# converter.net
KiCad netlist of a schematic drawn in Altium Designer
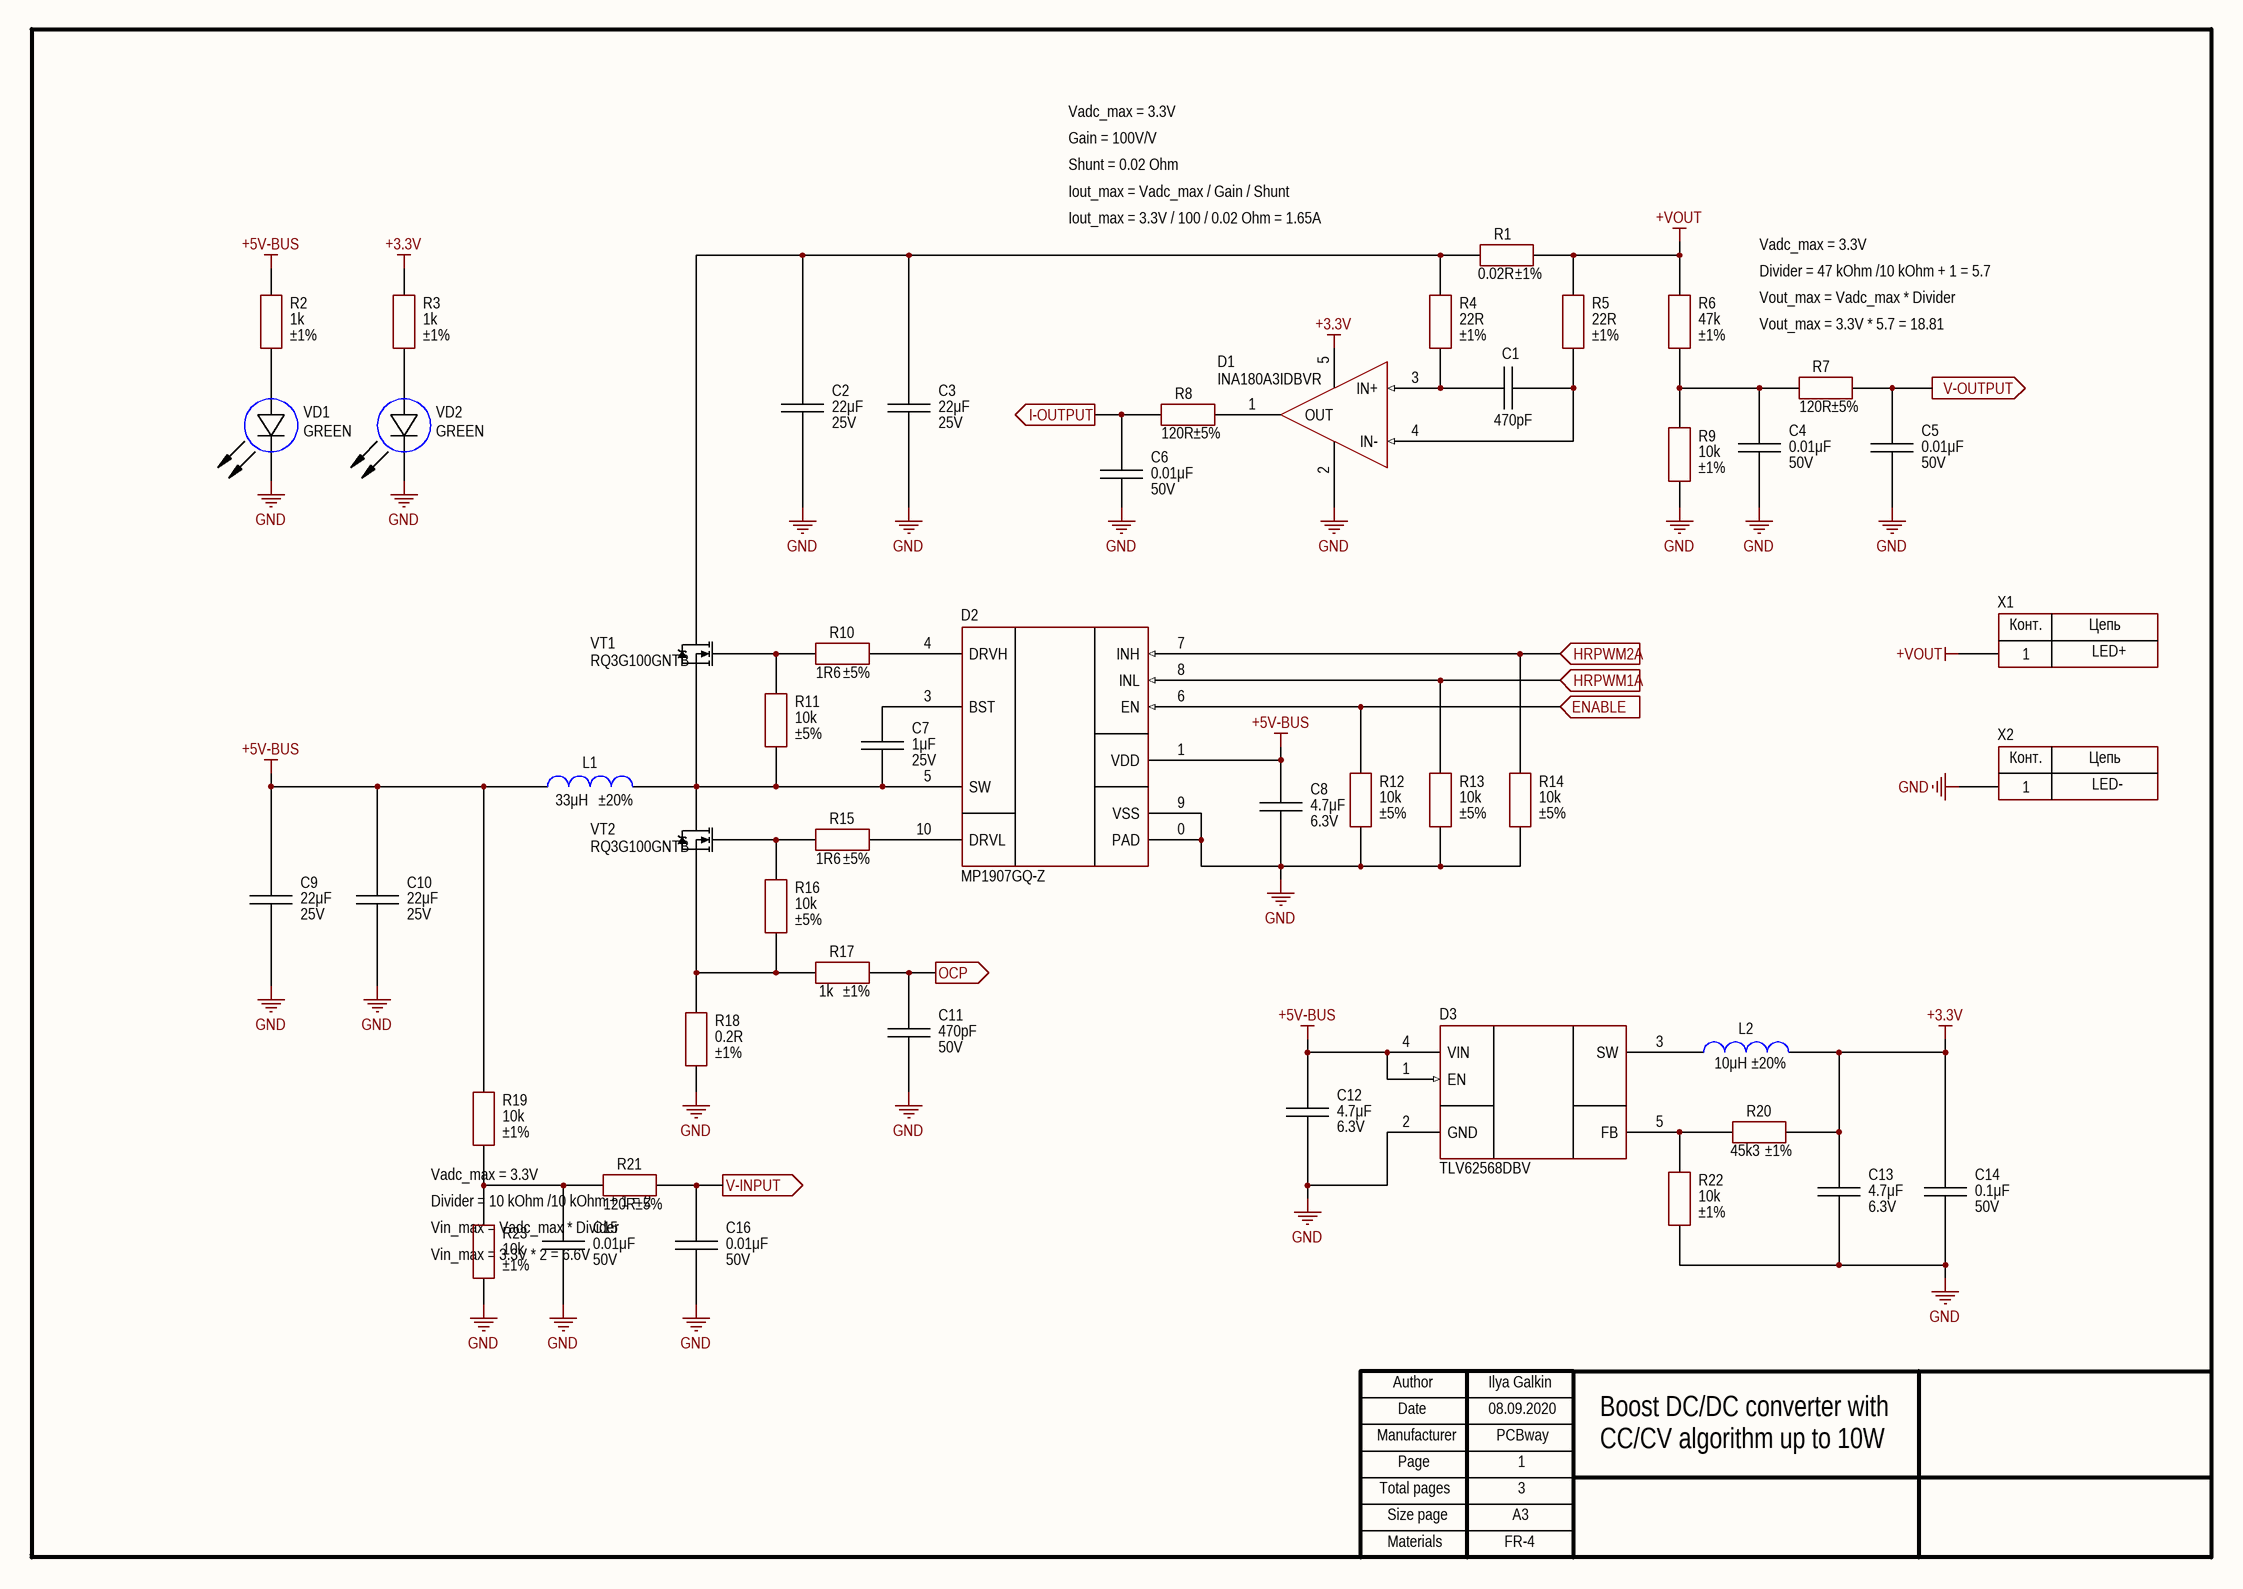
[diagram p0: converter.SchDoc]

(export (version "E")
  (design (tool "Eeschema 10.0.6"))
  (components
    (comp (ref "C1")
      (value "470pF")
      (footprint "CAP: 0603")
      (fields
        (field (name "MANUFACTURER") "Yageo")
        (field (name "PARTNUMBER") "CL10C471JB8NNNC")
        (field (name "VALUEMANUFACTURERPARTNUMBER") "Ceramic capacitor, 470pF, NPO, ±5%, 50V, 0603, -55...+125°C")
      )
      (libsource (lib "Capacitor") (part "Ceramic_0603"))
    )
    (comp (ref "C2")
      (value "22μF")
      (footprint "CAP: 1210")
      (fields
        (field (name "MANUFACTURER") "Samsung")
        (field (name "PARTNUMBER") "CL32B226KAJNNNE")
        (field (name "VALUEMANUFACTURERPARTNUMBER") "Ceramic capacitor, 22μF, X7R, ±10%, 25V, 1210, -55...+125°C")
        (field (name "VOLTAGE") "25V")
      )
      (libsource (lib "capacitor") (part "Ceramic_1210"))
    )
    (comp (ref "C3")
      (value "22μF")
      (footprint "CAP: 1210")
      (fields
        (field (name "MANUFACTURER") "Samsung")
        (field (name "PARTNUMBER") "CL32B226KAJNNNE")
        (field (name "VALUEMANUFACTURERPARTNUMBER") "Ceramic capacitor, 22μF, X7R, ±10%, 25V, 1210, -55...+125°C")
        (field (name "VOLTAGE") "25V")
      )
      (libsource (lib "capacitor") (part "Ceramic_1210"))
    )
    (comp (ref "C4")
      (value "0.01μF")
      (footprint "CAP: 0603")
      (fields
        (field (name "MANUFACTURER") "Samsung")
        (field (name "PARTNUMBER") "CL10B103KB8NNNC")
        (field (name "VALUEMANUFACTURERPARTNUMBER") "Ceramic capacitor, 0.01μF, X7R, ±10%, 50V, 0603, -55...+125°C")
        (field (name "VOLTAGE") "50V")
      )
      (libsource (lib "capacitor") (part "Ceramic_0603"))
    )
    (comp (ref "C5")
      (value "0.01μF")
      (footprint "CAP: 0603")
      (fields
        (field (name "MANUFACTURER") "Samsung")
        (field (name "PARTNUMBER") "CL10B103KB8NNNC")
        (field (name "VALUEMANUFACTURERPARTNUMBER") "Ceramic capacitor, 0.01μF, X7R, ±10%, 50V, 0603, -55...+125°C")
        (field (name "VOLTAGE") "50V")
      )
      (libsource (lib "capacitor") (part "Ceramic_0603"))
    )
    (comp (ref "C6")
      (value "0.01μF")
      (footprint "CAP: 0603")
      (fields
        (field (name "MANUFACTURER") "Samsung")
        (field (name "PARTNUMBER") "CL10B103KB8NNNC")
        (field (name "VALUEMANUFACTURERPARTNUMBER") "Ceramic capacitor, 0.01μF, X7R, ±10%, 50V, 0603, -55...+125°C")
        (field (name "VOLTAGE") "50V")
      )
      (libsource (lib "capacitor") (part "Ceramic_0603"))
    )
    (comp (ref "C7")
      (value "1μF")
      (footprint "CAP: 0603")
      (fields
        (field (name "MANUFACTURER") "Samsung")
        (field (name "PARTNUMBER") "CL10B105KA8NNNC")
        (field (name "VALUEMANUFACTURERPARTNUMBER") "Ceramic capacitor, 1μF, X7R, ±10%, 25V, 0603, -55...+125°C")
        (field (name "VOLTAGE") "25V")
      )
      (libsource (lib "capacitor") (part "Ceramic_0603"))
    )
    (comp (ref "C8")
      (value "4.7μF")
      (footprint "CAP: 0603")
      (fields
        (field (name "MANUFACTURER") "Samsung")
        (field (name "PARTNUMBER") "CL10B475KQ8NQNC")
        (field (name "VALUEMANUFACTURERPARTNUMBER") "Ceramic capacitor, 4.7μF, X7R, ±10%, 6.3V, 0603, -55...+125°C")
        (field (name "VOLTAGE") "6.3V")
      )
      (libsource (lib "capacitor") (part "Ceramic_0603"))
    )
    (comp (ref "C9")
      (value "22μF")
      (footprint "CAP: 1210")
      (fields
        (field (name "MANUFACTURER") "Samsung")
        (field (name "PARTNUMBER") "CL32B226KAJNNNE")
        (field (name "VALUEMANUFACTURERPARTNUMBER") "Ceramic capacitor, 22μF, X7R, ±10%, 25V, 1210, -55...+125°C")
        (field (name "VOLTAGE") "25V")
      )
      (libsource (lib "capacitor") (part "Ceramic_1210"))
    )
    (comp (ref "C10")
      (value "22μF")
      (footprint "CAP: 1210")
      (fields
        (field (name "MANUFACTURER") "Samsung")
        (field (name "PARTNUMBER") "CL32B226KAJNNNE")
        (field (name "VALUEMANUFACTURERPARTNUMBER") "Ceramic capacitor, 22μF, X7R, ±10%, 25V, 1210, -55...+125°C")
        (field (name "VOLTAGE") "25V")
      )
      (libsource (lib "capacitor") (part "Ceramic_1210"))
    )
    (comp (ref "C11")
      (value "470pF")
      (footprint "CAP: 0603")
      (fields
        (field (name "MANUFACTURER") "Yageo")
        (field (name "PARTNUMBER") "CL10C471JB8NNNC")
        (field (name "VALUEMANUFACTURERPARTNUMBER") "Ceramic capacitor, 470pF, NPO, ±5%, 50V, 0603, -55...+125°C")
        (field (name "VOLTAGE") "50V")
      )
      (libsource (lib "Capacitor") (part "Ceramic_0603"))
    )
    (comp (ref "C12")
      (value "4.7μF")
      (footprint "CAP: 0603")
      (fields
        (field (name "MANUFACTURER") "Samsung")
        (field (name "PARTNUMBER") "CL10B475KQ8NQNC")
        (field (name "VALUEMANUFACTURERPARTNUMBER") "Ceramic capacitor, 4.7μF, X7R, ±10%, 6.3V, 0603, -55...+125°C")
        (field (name "VOLTAGE") "6.3V")
      )
      (libsource (lib "capacitor") (part "Ceramic_0603"))
    )
    (comp (ref "C13")
      (value "4.7μF")
      (footprint "CAP: 0603")
      (fields
        (field (name "MANUFACTURER") "Samsung")
        (field (name "PARTNUMBER") "CL10B475KQ8NQNC")
        (field (name "VALUEMANUFACTURERPARTNUMBER") "Ceramic capacitor, 4.7μF, X7R, ±10%, 6.3V, 0603, -55...+125°C")
        (field (name "VOLTAGE") "6.3V")
      )
      (libsource (lib "capacitor") (part "Ceramic_0603"))
    )
    (comp (ref "C14")
      (value "0.1μF")
      (footprint "CAP: 0603")
      (fields
        (field (name "MANUFACTURER") "Samsung")
        (field (name "PARTNUMBER") "CL10B104KB8NNNL")
        (field (name "VALUEMANUFACTURERPARTNUMBER") "Ceramic capacitor, 0.1μF, X7R, ±10%, 50V, 0603, -55...+125°C")
        (field (name "VOLTAGE") "50V")
      )
      (libsource (lib "capacitor") (part "Ceramic_0603"))
    )
    (comp (ref "C15")
      (value "0.01μF")
      (footprint "CAP: 0603")
      (fields
        (field (name "MANUFACTURER") "Samsung")
        (field (name "PARTNUMBER") "CL10B103KB8NNNC")
        (field (name "VALUEMANUFACTURERPARTNUMBER") "Ceramic capacitor, 0.01μF, X7R, ±10%, 50V, 0603, -55...+125°C")
        (field (name "VOLTAGE") "50V")
      )
      (libsource (lib "capacitor") (part "Ceramic_0603"))
    )
    (comp (ref "C16")
      (value "0.01μF")
      (footprint "CAP: 0603")
      (fields
        (field (name "MANUFACTURER") "Samsung")
        (field (name "PARTNUMBER") "CL10B103KB8NNNC")
        (field (name "VALUEMANUFACTURERPARTNUMBER") "Ceramic capacitor, 0.01μF, X7R, ±10%, 50V, 0603, -55...+125°C")
        (field (name "VOLTAGE") "50V")
      )
      (libsource (lib "capacitor") (part "Ceramic_0603"))
    )
    (comp (ref "D1")
      (value "~")
      (footprint "SOT23-5")
      (description "Current monitor")
      (fields
        (field (name "MANUFACTURER") "Texas Instruments")
        (field (name "VALUEMANUFACTURERPARTNUMBER") "IC current monitor, ±1.5%, 100V/V, -0.3...+26V, -40...+125°C, SOT23-5")
        (field (name "PARTNUMBER") "INA180A3IDBVR")
      )
      (libsource (lib "ic-sensor") (part "INA180A3IDBVR"))
    )
    (comp (ref "D2")
      (value "~")
      (footprint "10-DFN")
      (description "Gate driver")
      (fields
        (field (name "MANUFACTURER") "Monolithic Power Systems")
        (field (name "VALUEMANUFACTURERPARTNUMBER") "Half-bridge gate driver, 100V, 500kHz, ±2.5A, supply 4.5...18V, -40...+125°C, 10-VFDFN (3x3)")
        (field (name "PARTNUMBER") "MP1907GQ-Z")
      )
      (libsource (lib "ic-gate-driver") (part "MP1907GQ-Z"))
    )
    (comp (ref "D3")
      (value "~")
      (footprint "SOT23-5")
      (description "Buck converter")
      (fields
        (field (name "MANUFACTURER") "Texas Instruments")
        (field (name "VALUEMANUFACTURERPARTNUMBER") "DC/DC buck converter, input 2.5...5.5V, 1.5MHz, output 0.6V, 1A, -40...+85°C, SOT23-5")
        (field (name "PARTNUMBER") "TLV62568DBV")
      )
      (libsource (lib "ic-power-supply") (part "TLV62568DBV"))
    )
    (comp (ref "L1")
      (value "33μH")
      (footprint "IND: SRP1038C")
      (fields
        (field (name "MANUFACTURER") "Bourns")
        (field (name "PARTNUMBER") "SRP1038C-330M")
        (field (name "VALUEMANUFACTURERPARTNUMBER") "Fixed inductor, 33μH, ±20%, SRP1038C series, 4A, -40...+125°C")
        (field (name "TOLERANCE") "±20%")
      )
      (libsource (lib "inductor") (part "Inductor_SRP1038C"))
    )
    (comp (ref "L2")
      (value "10μH")
      (footprint "IND: CD32")
      (fields
        (field (name "MANUFACTURER") "Codaca")
        (field (name "PARTNUMBER") "SDR0302-100ML")
        (field (name "VALUEMANUFACTURERPARTNUMBER") "Fixed inductor, 10μH, ±20%, SP32 series, 900mA, -40...+125°C")
        (field (name "TOLERANCE") "±20%")
      )
      (libsource (lib "inductor") (part "Inductor_CD32"))
    )
    (comp (ref "R1")
      (value "0.02R")
      (footprint "RES: 1206")
      (fields
        (field (name "MANUFACTURER") "Yageo")
        (field (name "PARTNUMBER") "PF1206FRF070R02L")
        (field (name "VALUEMANUFACTURERPARTNUMBER") "Resistor film, 0.02R, ±1%, 1206, 0.25W, -55...+125°C")
        (field (name "TOLERANCE") "±1%")
      )
      (libsource (lib "resistor") (part "Resistor_1206"))
    )
    (comp (ref "R2")
      (value "1k")
      (footprint "RES: 0603")
      (fields
        (field (name "MANUFACTURER") "Yageo")
        (field (name "PARTNUMBER") "RC0603FR-071KL")
        (field (name "VALUEMANUFACTURERPARTNUMBER") "Resistor film, 1k, ±1%, 0603, 0.1W, -55...+125°C")
        (field (name "TOLERANCE") "±1%")
      )
      (libsource (lib "resistor") (part "Resistor_0603"))
    )
    (comp (ref "R3")
      (value "1k")
      (footprint "RES: 0603")
      (fields
        (field (name "MANUFACTURER") "Yageo")
        (field (name "PARTNUMBER") "RC0603FR-071KL")
        (field (name "VALUEMANUFACTURERPARTNUMBER") "Resistor film, 1k, ±1%, 0603, 0.1W, -55...+125°C")
        (field (name "TOLERANCE") "±1%")
      )
      (libsource (lib "resistor") (part "Resistor_0603"))
    )
    (comp (ref "R4")
      (value "22R")
      (footprint "RES: 0603")
      (fields
        (field (name "MANUFACTURER") "Yageo")
        (field (name "PARTNUMBER") "RC0603FR-0722RL")
        (field (name "VALUEMANUFACTURERPARTNUMBER") "Resistor film, 22R, ±1%, 0603, 0.1W, -55...+125°C")
        (field (name "TOLERANCE") "±1%")
      )
      (libsource (lib "Resistor") (part "Resistor_0603"))
    )
    (comp (ref "R5")
      (value "22R")
      (footprint "RES: 0603")
      (fields
        (field (name "MANUFACTURER") "Yageo")
        (field (name "PARTNUMBER") "RC0603FR-0722RL")
        (field (name "VALUEMANUFACTURERPARTNUMBER") "Resistor film, 22R, ±1%, 0603, 0.1W, -55...+125°C")
        (field (name "TOLERANCE") "±1%")
      )
      (libsource (lib "Resistor") (part "Resistor_0603"))
    )
    (comp (ref "R6")
      (value "47k")
      (footprint "RES: 0603")
      (fields
        (field (name "MANUFACTURER") "Yageo")
        (field (name "PARTNUMBER") "RC0603FR-0747KL")
        (field (name "VALUEMANUFACTURERPARTNUMBER") "Resistor film, 47k, ±1%, 0603, 0.1W, -55...+125°C")
        (field (name "TOLERANCE") "±1%")
      )
      (libsource (lib "") (part "Resistor_0603_2"))
    )
    (comp (ref "R7")
      (value "120R")
      (footprint "RES: 0603")
      (fields
        (field (name "MANUFACTURER") "Yageo")
        (field (name "PARTNUMBER") "RC0603JR-07120RL")
        (field (name "VALUEMANUFACTURERPARTNUMBER") "Resistor film, 120R, ±5%, 0603, 0.1W, -55...+125°C")
        (field (name "TOLERANCE") "±5%")
      )
      (libsource (lib "") (part "Resistor_0603_1"))
    )
    (comp (ref "R8")
      (value "120R")
      (footprint "RES: 0603")
      (fields
        (field (name "MANUFACTURER") "Yageo")
        (field (name "PARTNUMBER") "RC0603JR-07120RL")
        (field (name "VALUEMANUFACTURERPARTNUMBER") "Resistor film, 120R, ±5%, 0603, 0.1W, -55...+125°C")
        (field (name "TOLERANCE") "±5%")
      )
      (libsource (lib "") (part "Resistor_0603_1"))
    )
    (comp (ref "R9")
      (value "10k")
      (footprint "RES: 0603")
      (fields
        (field (name "MANUFACTURER") "Yageo")
        (field (name "PARTNUMBER") "RC0603FR-0710KL")
        (field (name "VALUEMANUFACTURERPARTNUMBER") "Resistor film, 10k, ±1%, 0603, 0.1W, -55...+125°C")
        (field (name "TOLERANCE") "±1%")
      )
      (libsource (lib "resistor") (part "Resistor_0603"))
    )
    (comp (ref "R10")
      (value "1R6")
      (footprint "RES: 0603")
      (fields
        (field (name "MANUFACTURER") "Yageo")
        (field (name "PARTNUMBER") "RC0603JR-071R6L")
        (field (name "VALUEMANUFACTURERPARTNUMBER") "Resistor film, 1R6, ±5%, 0603, 0.1W, -55...+125°C")
        (field (name "TOLERANCE") "±5%")
      )
      (libsource (lib "") (part "Resistor_0603_1"))
    )
    (comp (ref "R11")
      (value "10k")
      (footprint "RES: 0603")
      (fields
        (field (name "MANUFACTURER") "Yageo")
        (field (name "PARTNUMBER") "RC0603JR-0710KL")
        (field (name "VALUEMANUFACTURERPARTNUMBER") "Resistor film, 10k, ±5%, 0603, 0.1W, -55...+125°C")
        (field (name "TOLERANCE") "±5%")
      )
      (libsource (lib "resistor") (part "Resistor_0603"))
    )
    (comp (ref "R12")
      (value "10k")
      (footprint "RES: 0603")
      (fields
        (field (name "MANUFACTURER") "Yageo")
        (field (name "PARTNUMBER") "RC0603JR-0710KL")
        (field (name "VALUEMANUFACTURERPARTNUMBER") "Resistor film, 10k, ±5%, 0603, 0.1W, -55...+125°C")
        (field (name "TOLERANCE") "±5%")
      )
      (libsource (lib "resistor") (part "Resistor_0603"))
    )
    (comp (ref "R13")
      (value "10k")
      (footprint "RES: 0603")
      (fields
        (field (name "MANUFACTURER") "Yageo")
        (field (name "PARTNUMBER") "RC0603JR-0710KL")
        (field (name "VALUEMANUFACTURERPARTNUMBER") "Resistor film, 10k, ±5%, 0603, 0.1W, -55...+125°C")
        (field (name "TOLERANCE") "±5%")
      )
      (libsource (lib "resistor") (part "Resistor_0603"))
    )
    (comp (ref "R14")
      (value "10k")
      (footprint "RES: 0603")
      (fields
        (field (name "MANUFACTURER") "Yageo")
        (field (name "PARTNUMBER") "RC0603JR-0710KL")
        (field (name "VALUEMANUFACTURERPARTNUMBER") "Resistor film, 10k, ±5%, 0603, 0.1W, -55...+125°C")
        (field (name "TOLERANCE") "±5%")
      )
      (libsource (lib "resistor") (part "Resistor_0603"))
    )
    (comp (ref "R15")
      (value "1R6")
      (footprint "RES: 0603")
      (fields
        (field (name "MANUFACTURER") "Yageo")
        (field (name "PARTNUMBER") "RC0603JR-071R6L")
        (field (name "VALUEMANUFACTURERPARTNUMBER") "Resistor film, 1R6, ±5%, 0603, 0.1W, -55...+125°C")
        (field (name "TOLERANCE") "±5%")
      )
      (libsource (lib "") (part "Resistor_0603_1"))
    )
    (comp (ref "R16")
      (value "10k")
      (footprint "RES: 0603")
      (fields
        (field (name "MANUFACTURER") "Yageo")
        (field (name "PARTNUMBER") "RC0603JR-0710KL")
        (field (name "VALUEMANUFACTURERPARTNUMBER") "Resistor film, 10k, ±5%, 0603, 0.1W, -55...+125°C")
        (field (name "TOLERANCE") "±5%")
      )
      (libsource (lib "resistor") (part "Resistor_0603"))
    )
    (comp (ref "R17")
      (value "1k")
      (footprint "RES: 0603")
      (fields
        (field (name "MANUFACTURER") "Yageo")
        (field (name "PARTNUMBER") "RC0603FR-071KL")
        (field (name "VALUEMANUFACTURERPARTNUMBER") "Resistor film, 1k, ±1%, 0603, 0.1W, -55...+125°C")
        (field (name "TOLERANCE") "±1%")
      )
      (libsource (lib "") (part "Resistor_0603_1"))
    )
    (comp (ref "R18")
      (value "0.2R")
      (footprint "RES: 1210")
      (fields
        (field (name "MANUFACTURER") "Yageo")
        (field (name "PARTNUMBER") "RL1210FR-070R2L")
        (field (name "VALUEMANUFACTURERPARTNUMBER") "Resistor film, 0.2R, ±1%, 1210, 0.5W, -55...+125°C")
        (field (name "TOLERANCE") "±1%")
      )
      (libsource (lib "resistor") (part "Resistor_1210"))
    )
    (comp (ref "R19")
      (value "10k")
      (footprint "RES: 0603")
      (fields
        (field (name "MANUFACTURER") "Yageo")
        (field (name "PARTNUMBER") "RC0603FR-0710KL")
        (field (name "VALUEMANUFACTURERPARTNUMBER") "Resistor film, 10k, ±1%, 0603, 0.1W, -55...+125°C")
        (field (name "TOLERANCE") "±1%")
      )
      (libsource (lib "resistor") (part "Resistor_0603"))
    )
    (comp (ref "R20")
      (value "45k3")
      (footprint "RES: 0603")
      (fields
        (field (name "MANUFACTURER") "Yageo")
        (field (name "PARTNUMBER") "RC0603FR-0745K3L")
        (field (name "VALUEMANUFACTURERPARTNUMBER") "Resistor film, 45k3, ±1%, 0603, 0.1W, -55...+125°C")
        (field (name "TOLERANCE") "±1%")
      )
      (libsource (lib "") (part "Resistor_0603_3"))
    )
    (comp (ref "R21")
      (value "120R")
      (footprint "RES: 0603")
      (fields
        (field (name "MANUFACTURER") "Yageo")
        (field (name "PARTNUMBER") "RC0603JR-07120RL")
        (field (name "VALUEMANUFACTURERPARTNUMBER") "Resistor film, 120R, ±5%, 0603, 0.1W, -55...+125°C")
        (field (name "TOLERANCE") "±5%")
      )
      (libsource (lib "") (part "Resistor_0603_1"))
    )
    (comp (ref "R22")
      (value "10k")
      (footprint "RES: 0603")
      (fields
        (field (name "MANUFACTURER") "Yageo")
        (field (name "PARTNUMBER") "RC0603FR-0710KL")
        (field (name "VALUEMANUFACTURERPARTNUMBER") "Resistor film, 10k, ±1%, 0603, 0.1W, -55...+125°C")
        (field (name "TOLERANCE") "±1%")
      )
      (libsource (lib "resistor") (part "Resistor_0603"))
    )
    (comp (ref "R23")
      (value "10k")
      (footprint "RES: 0603")
      (fields
        (field (name "MANUFACTURER") "Yageo")
        (field (name "PARTNUMBER") "RC0603FR-0710KL")
        (field (name "VALUEMANUFACTURERPARTNUMBER") "Resistor film, 10k, ±1%, 0603, 0.1W, -55...+125°C")
        (field (name "TOLERANCE") "±1%")
      )
      (libsource (lib "resistor") (part "Resistor_0603"))
    )
    (comp (ref "VD1")
      (value "~")
      (footprint "LED: 0603G")
      (fields
        (field (name "MANUFACTURER") "Wurth")
        (field (name "VALUEMANUFACTURERPARTNUMBER") "LED, 20mA, 2V, 0603, -55...+150°C")
        (field (name "PARTNUMBER") "150060VS75000")
        (field (name "COLOR") "GREEN")
      )
      (libsource (lib "Diode") (part "LED_single"))
    )
    (comp (ref "VD2")
      (value "~")
      (footprint "LED: 0603G")
      (fields
        (field (name "MANUFACTURER") "Wurth")
        (field (name "VALUEMANUFACTURERPARTNUMBER") "LED, 20mA, 2V, 0603, -55...+150°C")
        (field (name "PARTNUMBER") "150060VS75000")
        (field (name "COLOR") "GREEN")
      )
      (libsource (lib "Diode") (part "LED_single"))
    )
    (comp (ref "VT1")
      (value "~")
      (footprint "8-PowerWDFN")
      (fields
        (field (name "MANUFACTURER") "Rohm Semiconductor")
        (field (name "VALUEMANUFACTURERPARTNUMBER") "MOSFET N-channel transistor, 40V, 10A, 8.4nC, 2W, 14.3mOhm, 615pF, 8-PowerVDFN (3x3), -55...+150°C")
        (field (name "PARTNUMBER") "RQ3G100GNTB")
      )
      (libsource (lib "transistor") (part "MOSFET_N_123"))
    )
    (comp (ref "VT2")
      (value "~")
      (footprint "8-PowerWDFN")
      (fields
        (field (name "MANUFACTURER") "Rohm Semiconductor")
        (field (name "VALUEMANUFACTURERPARTNUMBER") "MOSFET N-channel transistor, 40V, 10A, 8.4nC, 2W, 14.3mOhm, 615pF, 8-PowerVDFN (3x3), -55...+150°C")
        (field (name "PARTNUMBER") "RQ3G100GNTB")
      )
      (libsource (lib "transistor") (part "MOSFET_N_123"))
    )
    (comp (ref "X1")
      (value "~")
      (footprint "CON: TH 1mm")
      (fields (field (name "VALUEMANUFACTURERPARTNUMBER") "Power connector, *, *"))
      (libsource (lib "connector") (part "Connector_single_power"))
    )
    (comp (ref "X2")
      (value "~")
      (footprint "CON: TH 1mm")
      (fields (field (name "VALUEMANUFACTURERPARTNUMBER") "Power connector, *, *"))
      (libsource (lib "connector") (part "Connector_single_power"))
    )
  )
  (nets
    (net (code "1") (name "+3.3V") (class "Default")
      (node (ref "C13") (pin "2") (pinfunction "2_2") (pintype "passive"))
      (node (ref "C14") (pin "2") (pinfunction "2_2") (pintype "passive"))
      (node (ref "D1") (pin "5") (pinfunction "V+_5") (pintype "power_in"))
      (node (ref "L2") (pin "1") (pinfunction "1_1") (pintype "passive"))
      (node (ref "R20") (pin "1") (pinfunction "1_1") (pintype "passive"))
      (node (ref "R3") (pin "2") (pinfunction "2_2") (pintype "passive"))
    )
    (net (code "2") (name "+5V-BUS") (class "Default")
      (node (ref "C10") (pin "2") (pinfunction "2_2") (pintype "passive"))
      (node (ref "C12") (pin "2") (pinfunction "2_2") (pintype "passive"))
      (node (ref "C8") (pin "2") (pinfunction "2_2") (pintype "passive"))
      (node (ref "C9") (pin "2") (pinfunction "2_2") (pintype "passive"))
      (node (ref "D2") (pin "1") (pinfunction "VDD_1") (pintype "passive"))
      (node (ref "D3") (pin "1") (pinfunction "EN_1") (pintype "input"))
      (node (ref "D3") (pin "4") (pinfunction "VIN_4") (pintype "passive"))
      (node (ref "L1") (pin "2") (pinfunction "2_2") (pintype "passive"))
      (node (ref "R19") (pin "2") (pinfunction "2_2") (pintype "passive"))
      (node (ref "R2") (pin "2") (pinfunction "2_2") (pintype "passive"))
    )
    (net (code "3") (name "+VOUT") (class "Default")
      (node (ref "R1") (pin "2") (pinfunction "2_2") (pintype "passive"))
      (node (ref "R5") (pin "2") (pinfunction "2_2") (pintype "passive"))
      (node (ref "R6") (pin "1") (pinfunction "1_1") (pintype "passive"))
      (node (ref "X1") (pin "1") (pinfunction "1_1") (pintype "passive"))
    )
    (net (code "4") (name "/ENABLE") (class "Default")
      (node (ref "D2") (pin "6") (pinfunction "EN_6") (pintype "input"))
      (node (ref "R12") (pin "2") (pinfunction "2_2") (pintype "passive"))
    )
    (net (code "5") (name "/HRPWM1A") (class "Default")
      (node (ref "D2") (pin "8") (pinfunction "INL_8") (pintype "input"))
      (node (ref "R13") (pin "2") (pinfunction "2_2") (pintype "passive"))
    )
    (net (code "6") (name "/HRPWM2A") (class "Default")
      (node (ref "D2") (pin "7") (pinfunction "INH_7") (pintype "input"))
      (node (ref "R14") (pin "2") (pinfunction "2_2") (pintype "passive"))
    )
    (net (code "7") (name "/I-OUTPUT") (class "Default")
      (node (ref "C6") (pin "2") (pinfunction "2_2") (pintype "passive"))
      (node (ref "R8") (pin "1") (pinfunction "1_1") (pintype "passive"))
    )
    (net (code "8") (name "/OCP") (class "Default")
      (node (ref "C11") (pin "1") (pinfunction "1_1") (pintype "power_in"))
      (node (ref "R17") (pin "2") (pinfunction "2_2") (pintype "passive"))
    )
    (net (code "9") (name "/V-INPUT") (class "Default")
      (node (ref "C16") (pin "2") (pinfunction "2_2") (pintype "passive"))
      (node (ref "R21") (pin "2") (pinfunction "2_2") (pintype "passive"))
    )
    (net (code "10") (name "/V-OUTPUT") (class "Default")
      (node (ref "C5") (pin "2") (pinfunction "2_2") (pintype "passive"))
      (node (ref "R7") (pin "2") (pinfunction "2_2") (pintype "passive"))
    )
    (net (code "11") (name "GND") (class "Default")
      (node (ref "C10") (pin "1") (pinfunction "1_1") (pintype "passive"))
      (node (ref "C11") (pin "2") (pinfunction "2_2") (pintype "power_in"))
      (node (ref "C12") (pin "1") (pinfunction "1_1") (pintype "passive"))
      (node (ref "C13") (pin "1") (pinfunction "1_1") (pintype "passive"))
      (node (ref "C14") (pin "1") (pinfunction "1_1") (pintype "passive"))
      (node (ref "C15") (pin "1") (pinfunction "1_1") (pintype "passive"))
      (node (ref "C16") (pin "1") (pinfunction "1_1") (pintype "passive"))
      (node (ref "C2") (pin "1") (pinfunction "1_1") (pintype "passive"))
      (node (ref "C3") (pin "1") (pinfunction "1_1") (pintype "passive"))
      (node (ref "C4") (pin "1") (pinfunction "1_1") (pintype "passive"))
      (node (ref "C5") (pin "1") (pinfunction "1_1") (pintype "passive"))
      (node (ref "C6") (pin "1") (pinfunction "1_1") (pintype "passive"))
      (node (ref "C8") (pin "1") (pinfunction "1_1") (pintype "passive"))
      (node (ref "C9") (pin "1") (pinfunction "1_1") (pintype "passive"))
      (node (ref "D1") (pin "2") (pinfunction "V-_2") (pintype "power_in"))
      (node (ref "D2") (pin "0") (pinfunction "PAD_0") (pintype "passive"))
      (node (ref "D2") (pin "9") (pinfunction "VSS_9") (pintype "passive"))
      (node (ref "D3") (pin "2") (pinfunction "GND_2") (pintype "passive"))
      (node (ref "R12") (pin "1") (pinfunction "1_1") (pintype "passive"))
      (node (ref "R13") (pin "1") (pinfunction "1_1") (pintype "passive"))
      (node (ref "R14") (pin "1") (pinfunction "1_1") (pintype "passive"))
      (node (ref "R18") (pin "1") (pinfunction "1_1") (pintype "passive"))
      (node (ref "R22") (pin "1") (pinfunction "1_1") (pintype "passive"))
      (node (ref "R23") (pin "1") (pinfunction "1_1") (pintype "passive"))
      (node (ref "R9") (pin "1") (pinfunction "1_1") (pintype "passive"))
      (node (ref "VD1") (pin "2") (pinfunction "C_2") (pintype "passive"))
      (node (ref "VD2") (pin "2") (pinfunction "C_2") (pintype "passive"))
      (node (ref "X2") (pin "1") (pinfunction "1_1") (pintype "passive"))
    )
    (net (code "12") (name "Net-(C4-Pad2)") (class "Default")
      (node (ref "C4") (pin "2") (pinfunction "2_2") (pintype "passive"))
      (node (ref "R6") (pin "2") (pinfunction "2_2") (pintype "passive"))
      (node (ref "R7") (pin "1") (pinfunction "1_1") (pintype "passive"))
      (node (ref "R9") (pin "2") (pinfunction "2_2") (pintype "passive"))
    )
    (net (code "13") (name "Net-(C15-Pad2)") (class "Default")
      (node (ref "C15") (pin "2") (pinfunction "2_2") (pintype "passive"))
      (node (ref "R19") (pin "1") (pinfunction "1_1") (pintype "passive"))
      (node (ref "R21") (pin "1") (pinfunction "1_1") (pintype "passive"))
      (node (ref "R23") (pin "2") (pinfunction "2_2") (pintype "passive"))
    )
    (net (code "14") (name "Net-(D1-IN+)") (class "Default")
      (node (ref "C1") (pin "2") (pinfunction "2_2") (pintype "power_in"))
      (node (ref "D1") (pin "3") (pinfunction "IN+_3") (pintype "input"))
      (node (ref "R4") (pin "1") (pinfunction "1_1") (pintype "passive"))
    )
    (net (code "15") (name "Net-(D1-IN-)") (class "Default")
      (node (ref "C1") (pin "1") (pinfunction "1_1") (pintype "power_in"))
      (node (ref "D1") (pin "4") (pinfunction "IN-_4") (pintype "input"))
      (node (ref "R5") (pin "1") (pinfunction "1_1") (pintype "passive"))
    )
    (net (code "16") (name "Net-(D1-OUT)") (class "Default")
      (node (ref "D1") (pin "1") (pinfunction "OUT_1") (pintype "power_in"))
      (node (ref "R8") (pin "2") (pinfunction "2_2") (pintype "passive"))
    )
    (net (code "17") (name "Net-(D2-BST)") (class "Default")
      (node (ref "C7") (pin "2") (pinfunction "2_2") (pintype "passive"))
      (node (ref "D2") (pin "3") (pinfunction "BST_3") (pintype "passive"))
    )
    (net (code "18") (name "Net-(D2-DRVH)") (class "Default")
      (node (ref "D2") (pin "4") (pinfunction "DRVH_4") (pintype "passive"))
      (node (ref "R10") (pin "2") (pinfunction "2_2") (pintype "passive"))
    )
    (net (code "19") (name "Net-(D2-DRVL)") (class "Default")
      (node (ref "D2") (pin "10") (pinfunction "DRVL_10") (pintype "passive"))
      (node (ref "R15") (pin "2") (pinfunction "2_2") (pintype "passive"))
    )
    (net (code "20") (name "Net-(D2-SW)") (class "Default")
      (node (ref "C7") (pin "1") (pinfunction "1_1") (pintype "passive"))
      (node (ref "D2") (pin "5") (pinfunction "SW_5") (pintype "passive"))
      (node (ref "L1") (pin "1") (pinfunction "1_1") (pintype "passive"))
      (node (ref "R11") (pin "1") (pinfunction "1_1") (pintype "passive"))
      (node (ref "VT1") (pin "3") (pinfunction "S_3") (pintype "passive"))
      (node (ref "VT2") (pin "2") (pinfunction "D_2") (pintype "passive"))
    )
    (net (code "21") (name "Net-(D3-FB)") (class "Default")
      (node (ref "D3") (pin "5") (pinfunction "FB_5") (pintype "passive"))
      (node (ref "R20") (pin "2") (pinfunction "2_2") (pintype "passive"))
      (node (ref "R22") (pin "2") (pinfunction "2_2") (pintype "passive"))
    )
    (net (code "22") (name "Net-(D3-SW)") (class "Default")
      (node (ref "D3") (pin "3") (pinfunction "SW_3") (pintype "passive"))
      (node (ref "L2") (pin "2") (pinfunction "2_2") (pintype "passive"))
    )
    (net (code "23") (name "Net-(VD1-A)") (class "Default")
      (node (ref "R2") (pin "1") (pinfunction "1_1") (pintype "passive"))
      (node (ref "VD1") (pin "1") (pinfunction "A_1") (pintype "passive"))
    )
    (net (code "24") (name "Net-(VD2-A)") (class "Default")
      (node (ref "R3") (pin "1") (pinfunction "1_1") (pintype "passive"))
      (node (ref "VD2") (pin "1") (pinfunction "A_1") (pintype "passive"))
    )
    (net (code "25") (name "Net-(VT1-D)") (class "Default")
      (node (ref "C2") (pin "2") (pinfunction "2_2") (pintype "passive"))
      (node (ref "C3") (pin "2") (pinfunction "2_2") (pintype "passive"))
      (node (ref "R1") (pin "1") (pinfunction "1_1") (pintype "passive"))
      (node (ref "R4") (pin "2") (pinfunction "2_2") (pintype "passive"))
      (node (ref "VT1") (pin "2") (pinfunction "D_2") (pintype "passive"))
    )
    (net (code "26") (name "Net-(VT1-G)") (class "Default")
      (node (ref "R10") (pin "1") (pinfunction "1_1") (pintype "passive"))
      (node (ref "R11") (pin "2") (pinfunction "2_2") (pintype "passive"))
      (node (ref "VT1") (pin "1") (pinfunction "G_1") (pintype "passive"))
    )
    (net (code "27") (name "Net-(VT2-G)") (class "Default")
      (node (ref "R15") (pin "1") (pinfunction "1_1") (pintype "passive"))
      (node (ref "R16") (pin "2") (pinfunction "2_2") (pintype "passive"))
      (node (ref "VT2") (pin "1") (pinfunction "G_1") (pintype "passive"))
    )
    (net (code "28") (name "Net-(VT2-S)") (class "Default")
      (node (ref "R16") (pin "1") (pinfunction "1_1") (pintype "passive"))
      (node (ref "R17") (pin "1") (pinfunction "1_1") (pintype "passive"))
      (node (ref "R18") (pin "2") (pinfunction "2_2") (pintype "passive"))
      (node (ref "VT2") (pin "3") (pinfunction "S_3") (pintype "passive"))
    )
  )
)
